# SparkFun_Music_Instrument_Shield.net
KiCad netlist of a schematic drawn in EAGLE
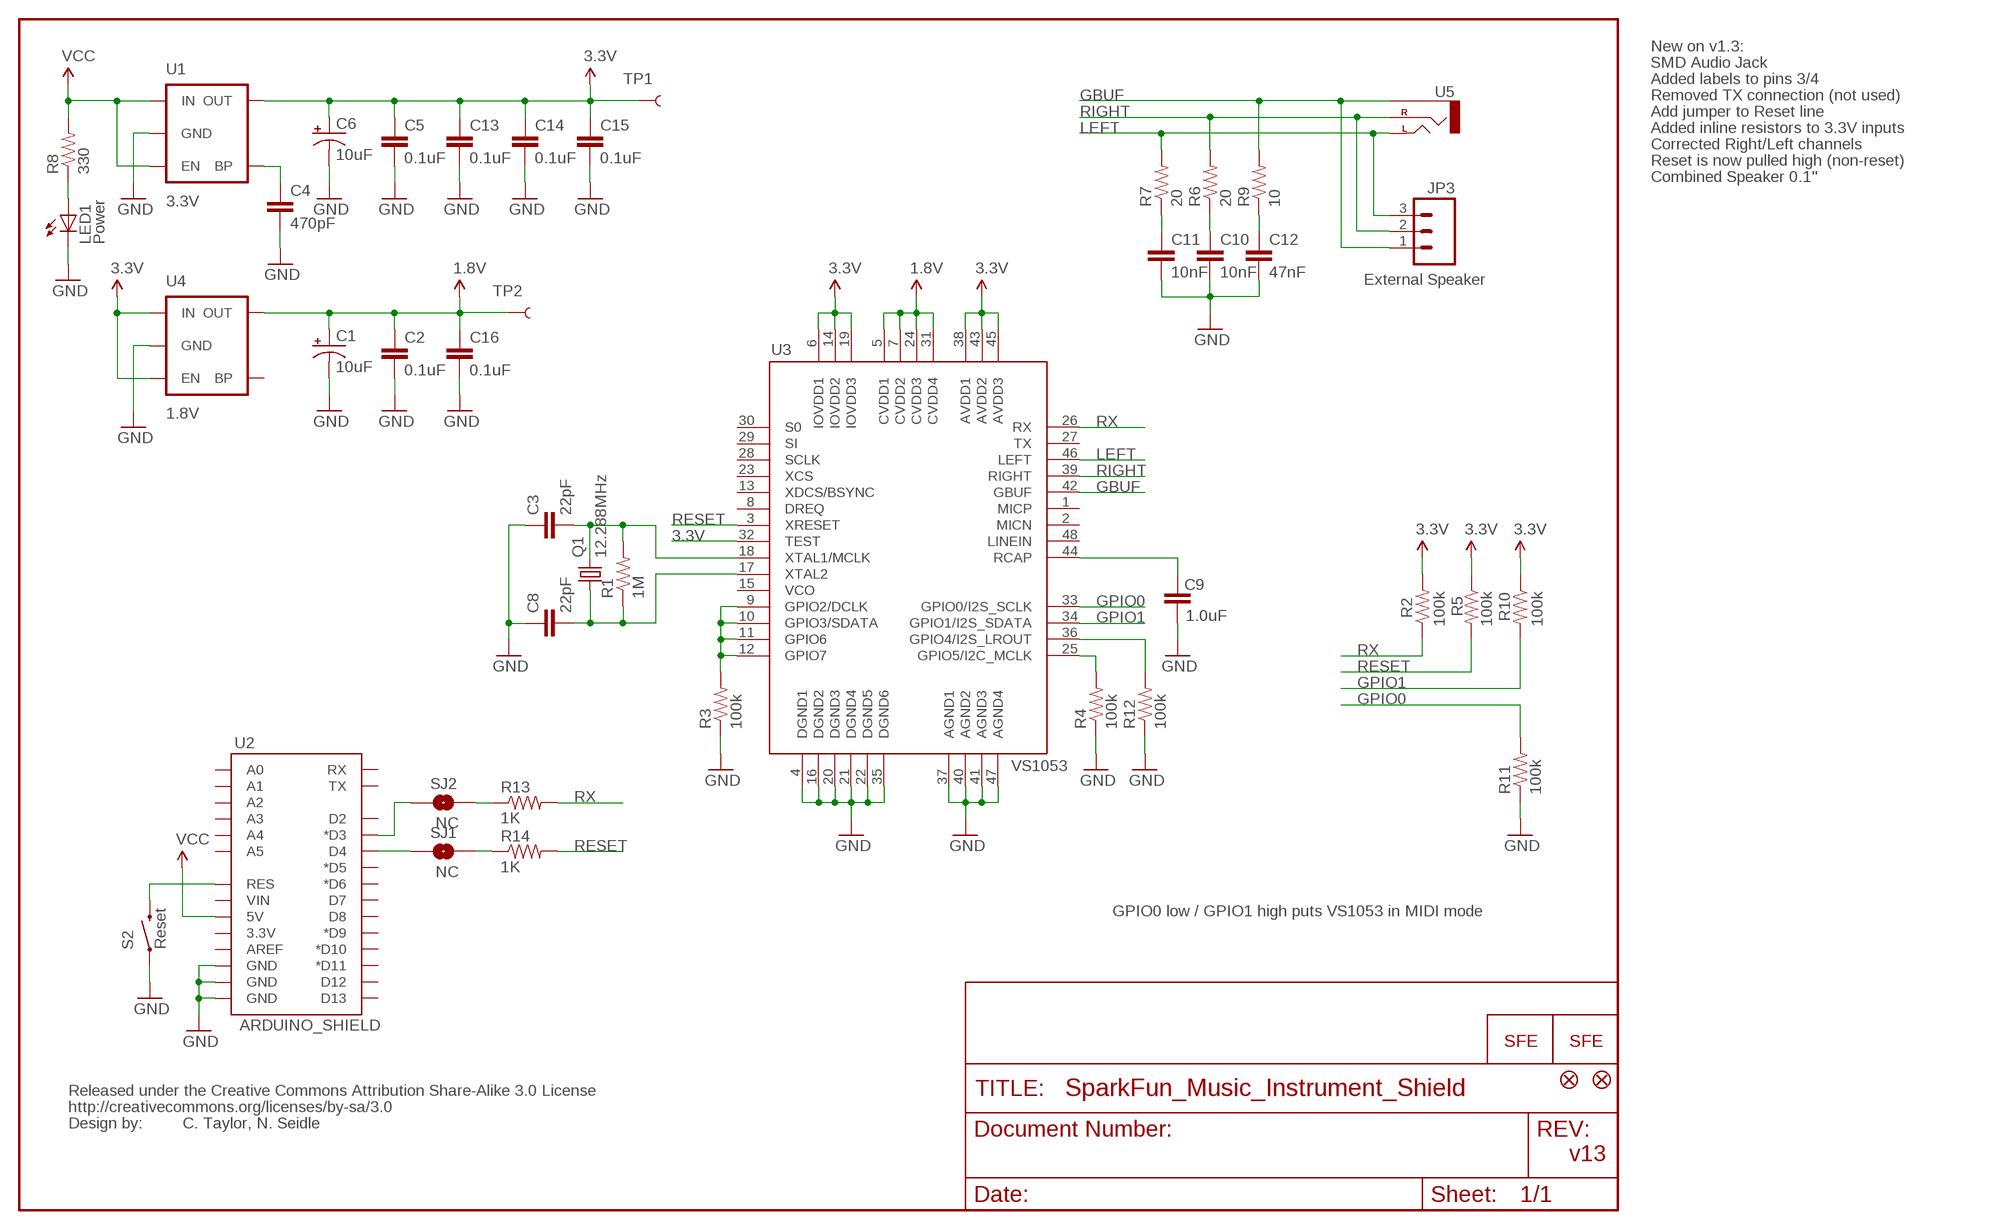
[diagram p0: schematic, sheet 1]

(export (version "E")
  (design (tool "Eeschema 10.0.6"))
  (components
    (comp (ref "C1")
      (value "10uF")
      (footprint "eagle-import:EIA3216")
      (libsource (lib "eagle-import") (part "CAP_POL1206"))
    )
    (comp (ref "C2")
      (value "0.1uF")
      (footprint "eagle-import:0402-CAP")
      (libsource (lib "eagle-import") (part "CAP0402-CAP"))
    )
    (comp (ref "C3")
      (value "22pF")
      (footprint "eagle-import:0402-CAP")
      (libsource (lib "eagle-import") (part "CAP0402-CAP"))
    )
    (comp (ref "C4")
      (value "470pF")
      (footprint "eagle-import:0402-CAP")
      (libsource (lib "eagle-import") (part "CAP0402-CAP"))
    )
    (comp (ref "C5")
      (value "0.1uF")
      (footprint "eagle-import:0402-CAP")
      (libsource (lib "eagle-import") (part "CAP0402-CAP"))
    )
    (comp (ref "C6")
      (value "10uF")
      (footprint "eagle-import:EIA3216")
      (libsource (lib "eagle-import") (part "CAP_POL1206"))
    )
    (comp (ref "C8")
      (value "22pF")
      (footprint "eagle-import:0402-CAP")
      (libsource (lib "eagle-import") (part "CAP0402-CAP"))
    )
    (comp (ref "C9")
      (value "1.0uF")
      (footprint "eagle-import:0402-CAP")
      (libsource (lib "eagle-import") (part "CAP0402-CAP"))
    )
    (comp (ref "C10")
      (value "10nF")
      (footprint "eagle-import:0402-CAP")
      (libsource (lib "eagle-import") (part "CAP0402-CAP"))
    )
    (comp (ref "C11")
      (value "10nF")
      (footprint "eagle-import:0402-CAP")
      (libsource (lib "eagle-import") (part "CAP0402-CAP"))
    )
    (comp (ref "C12")
      (value "47nF")
      (footprint "eagle-import:0402-CAP")
      (libsource (lib "eagle-import") (part "CAP0402-CAP"))
    )
    (comp (ref "C13")
      (value "0.1uF")
      (footprint "eagle-import:0402-CAP")
      (libsource (lib "eagle-import") (part "CAP0402-CAP"))
    )
    (comp (ref "C14")
      (value "0.1uF")
      (footprint "eagle-import:0402-CAP")
      (libsource (lib "eagle-import") (part "CAP0402-CAP"))
    )
    (comp (ref "C15")
      (value "0.1uF")
      (footprint "eagle-import:0402-CAP")
      (libsource (lib "eagle-import") (part "CAP0402-CAP"))
    )
    (comp (ref "C16")
      (value "0.1uF")
      (footprint "eagle-import:0402-CAP")
      (libsource (lib "eagle-import") (part "CAP0402-CAP"))
    )
    (comp (ref "JP3")
      (value "External Speaker")
      (footprint "eagle-import:1X03")
      (libsource (lib "eagle-import") (part "M03PTH"))
    )
    (comp (ref "LED1")
      (value "Power")
      (footprint "eagle-import:LED-0603")
      (libsource (lib "eagle-import") (part "LED0603"))
    )
    (comp (ref "Q1")
      (value "12.288MHz")
      (footprint "eagle-import:CRYSTAL-SMD-5X3")
      (libsource (lib "eagle-import") (part "CRYSTAL5X3"))
    )
    (comp (ref "R1")
      (value "1M")
      (footprint "eagle-import:0402-RES")
      (libsource (lib "eagle-import") (part "RESISTOR0402-RES"))
    )
    (comp (ref "R2")
      (value "100k")
      (footprint "eagle-import:0402-RES")
      (libsource (lib "eagle-import") (part "RESISTOR0402-RES"))
    )
    (comp (ref "R3")
      (value "100k")
      (footprint "eagle-import:0402-RES")
      (libsource (lib "eagle-import") (part "RESISTOR0402-RES"))
    )
    (comp (ref "R4")
      (value "100k")
      (footprint "eagle-import:0402-RES")
      (libsource (lib "eagle-import") (part "RESISTOR0402-RES"))
    )
    (comp (ref "R5")
      (value "100k")
      (footprint "eagle-import:0402-RES")
      (libsource (lib "eagle-import") (part "RESISTOR0402-RES"))
    )
    (comp (ref "R6")
      (value "20")
      (footprint "eagle-import:0402-RES")
      (libsource (lib "eagle-import") (part "RESISTOR0402-RES"))
    )
    (comp (ref "R7")
      (value "20")
      (footprint "eagle-import:0402-RES")
      (libsource (lib "eagle-import") (part "RESISTOR0402-RES"))
    )
    (comp (ref "R8")
      (value "330")
      (footprint "eagle-import:0402-RES")
      (libsource (lib "eagle-import") (part "RESISTOR0402-RES"))
    )
    (comp (ref "R9")
      (value "10")
      (footprint "eagle-import:0402-RES")
      (libsource (lib "eagle-import") (part "RESISTOR0402-RES"))
    )
    (comp (ref "R10")
      (value "100k")
      (footprint "eagle-import:0402-RES")
      (libsource (lib "eagle-import") (part "RESISTOR0402-RES"))
    )
    (comp (ref "R11")
      (value "100k")
      (footprint "eagle-import:0402-RES")
      (libsource (lib "eagle-import") (part "RESISTOR0402-RES"))
    )
    (comp (ref "R12")
      (value "100k")
      (footprint "eagle-import:0402-RES")
      (libsource (lib "eagle-import") (part "RESISTOR0402-RES"))
    )
    (comp (ref "R13")
      (value "1K")
      (footprint "eagle-import:0402-RES")
      (libsource (lib "eagle-import") (part "RESISTOR0402-RES"))
    )
    (comp (ref "R14")
      (value "1K")
      (footprint "eagle-import:0402-RES")
      (libsource (lib "eagle-import") (part "RESISTOR0402-RES"))
    )
    (comp (ref "S2")
      (value "Reset")
      (footprint "eagle-import:TACTILE_SWITCH_SMD")
      (libsource (lib "eagle-import") (part "SWITCH-MOMENTARY-2SMD"))
    )
    (comp (ref "SJ1")
      (value "NC")
      (footprint "eagle-import:SJ_2S-TRACE")
      (libsource (lib "eagle-import") (part "SOLDERJUMPERTRACE"))
    )
    (comp (ref "SJ2")
      (value "NC")
      (footprint "eagle-import:SJ_2S-TRACE")
      (libsource (lib "eagle-import") (part "SOLDERJUMPERTRACE"))
    )
    (comp (ref "TP1")
      (value "TEST-POINT3X5")
      (footprint "eagle-import:PAD.03X.05")
      (libsource (lib "eagle-import") (part "TEST-POINT3X5"))
    )
    (comp (ref "TP2")
      (value "TEST-POINT3X5")
      (footprint "eagle-import:PAD.03X.05")
      (libsource (lib "eagle-import") (part "TEST-POINT3X5"))
    )
    (comp (ref "U$3")
      (value "CREATIVE_COMMONS")
      (footprint "eagle-import:CREATIVE_COMMONS")
      (libsource (lib "eagle-import") (part "CREATIVE_COMMONS"))
    )
    (comp (ref "U$4")
      (value "FIDUCIAL1X2")
      (footprint "eagle-import:FIDUCIAL-1X2")
      (libsource (lib "eagle-import") (part "FIDUCIAL1X2"))
    )
    (comp (ref "U$5")
      (value "FIDUCIAL1X2")
      (footprint "eagle-import:FIDUCIAL-1X2")
      (libsource (lib "eagle-import") (part "FIDUCIAL1X2"))
    )
    (comp (ref "U$7")
      (value "LOGO-SFENEW")
      (footprint "eagle-import:SFE-NEW-WEBLOGO")
      (libsource (lib "eagle-import") (part "LOGO-SFENEW"))
    )
    (comp (ref "U$8")
      (value "LOGO-SFENEW")
      (footprint "eagle-import:SFE-NEW-WEBLOGO")
      (libsource (lib "eagle-import") (part "LOGO-SFENEW"))
    )
    (comp (ref "U1")
      (value "3.3V")
      (footprint "eagle-import:SOT23-5")
      (libsource (lib "eagle-import") (part "V_REG_LDOSMD"))
    )
    (comp (ref "U2")
      (value "ARDUINO_SHIELD")
      (footprint "eagle-import:DUEMILANOVE_SHIELD")
      (libsource (lib "eagle-import") (part "ARDUINO_SHIELDLABEL"))
    )
    (comp (ref "U3")
      (value "VS1053")
      (footprint "eagle-import:LQFP-48")
      (libsource (lib "eagle-import") (part "VS1033"))
    )
    (comp (ref "U4")
      (value "1.8V")
      (footprint "eagle-import:SC70")
      (libsource (lib "eagle-import") (part "V_REG_LDOSMD2"))
    )
    (comp (ref "U5")
      (value "AUDIO-JACKSMD2")
      (footprint "eagle-import:AUDIO-JACK-3.5MM-SMD")
      (libsource (lib "eagle-import") (part "AUDIO-JACKSMD2"))
    )
  )
  (nets
    (net (code "1") (name "/GBUF") (class "Default")
      (node (ref "JP3") (pin "1") (pinfunction "1_1") (pintype "passive"))
      (node (ref "R9") (pin "2") (pinfunction "2_2") (pintype "passive"))
      (node (ref "U3") (pin "42") (pinfunction "GBUF_42") (pintype "bidirectional"))
      (node (ref "U5") (pin "SLEEVE") (pinfunction "SLEEVE_SLEEVE") (pintype "bidirectional"))
    )
    (net (code "2") (name "/GPIO0") (class "Default")
      (node (ref "R11") (pin "2") (pinfunction "2_2") (pintype "passive"))
      (node (ref "U3") (pin "33") (pinfunction "GPIO0/I2S_SCLK_33") (pintype "bidirectional"))
    )
    (net (code "3") (name "/GPIO1") (class "Default")
      (node (ref "R10") (pin "2") (pinfunction "2_2") (pintype "passive"))
      (node (ref "U3") (pin "34") (pinfunction "GPIO1/I2S_SDATA_34") (pintype "bidirectional"))
    )
    (net (code "4") (name "/LEFT") (class "Default")
      (node (ref "JP3") (pin "3") (pinfunction "3_3") (pintype "passive"))
      (node (ref "R7") (pin "2") (pinfunction "2_2") (pintype "passive"))
      (node (ref "U3") (pin "46") (pinfunction "LEFT_46") (pintype "bidirectional"))
      (node (ref "U5") (pin "TIP") (pinfunction "LEFT_TIP") (pintype "bidirectional"))
    )
    (net (code "5") (name "/RESET") (class "Default")
      (node (ref "R14") (pin "2") (pinfunction "2_2") (pintype "passive"))
      (node (ref "R5") (pin "2") (pinfunction "2_2") (pintype "passive"))
      (node (ref "U3") (pin "3") (pinfunction "XRESET_3") (pintype "bidirectional"))
    )
    (net (code "6") (name "/RIGHT") (class "Default")
      (node (ref "JP3") (pin "2") (pinfunction "2_2") (pintype "passive"))
      (node (ref "R6") (pin "2") (pinfunction "2_2") (pintype "passive"))
      (node (ref "U3") (pin "39") (pinfunction "RIGHT_39") (pintype "bidirectional"))
      (node (ref "U5") (pin "RING") (pinfunction "RIGHT_RING") (pintype "bidirectional"))
    )
    (net (code "7") (name "/RX") (class "Default")
      (node (ref "R13") (pin "2") (pinfunction "2_2") (pintype "passive"))
      (node (ref "R2") (pin "1") (pinfunction "1_1") (pintype "passive"))
      (node (ref "U3") (pin "26") (pinfunction "RX_26") (pintype "bidirectional"))
    )
    (net (code "8") (name "1.8V") (class "Default")
      (node (ref "C1") (pin "A") (pinfunction "+_A") (pintype "passive"))
      (node (ref "C16") (pin "1") (pinfunction "1_1") (pintype "passive"))
      (node (ref "C2") (pin "1") (pinfunction "1_1") (pintype "passive"))
      (node (ref "TP2") (pin "P$1") (pinfunction "1_P$1") (pintype "bidirectional"))
      (node (ref "U3") (pin "24") (pinfunction "CVDD3_24") (pintype "bidirectional"))
      (node (ref "U3") (pin "31") (pinfunction "CVDD4_31") (pintype "bidirectional"))
      (node (ref "U3") (pin "5") (pinfunction "CVDD1_5") (pintype "bidirectional"))
      (node (ref "U3") (pin "7") (pinfunction "CVDD2_7") (pintype "bidirectional"))
      (node (ref "U4") (pin "5") (pinfunction "OUT_5") (pintype "passive"))
    )
    (net (code "9") (name "3.3V") (class "Default")
      (node (ref "C13") (pin "1") (pinfunction "1_1") (pintype "passive"))
      (node (ref "C14") (pin "1") (pinfunction "1_1") (pintype "passive"))
      (node (ref "C15") (pin "1") (pinfunction "1_1") (pintype "passive"))
      (node (ref "C5") (pin "1") (pinfunction "1_1") (pintype "passive"))
      (node (ref "C6") (pin "A") (pinfunction "+_A") (pintype "passive"))
      (node (ref "R10") (pin "1") (pinfunction "1_1") (pintype "passive"))
      (node (ref "R2") (pin "2") (pinfunction "2_2") (pintype "passive"))
      (node (ref "R5") (pin "1") (pinfunction "1_1") (pintype "passive"))
      (node (ref "TP1") (pin "P$1") (pinfunction "1_P$1") (pintype "bidirectional"))
      (node (ref "U1") (pin "5") (pinfunction "OUT_5") (pintype "passive"))
      (node (ref "U3") (pin "14") (pinfunction "IOVDD2_14") (pintype "bidirectional"))
      (node (ref "U3") (pin "19") (pinfunction "IOVDD3_19") (pintype "bidirectional"))
      (node (ref "U3") (pin "32") (pinfunction "TEST_32") (pintype "bidirectional"))
      (node (ref "U3") (pin "38") (pinfunction "AVDD1_38") (pintype "bidirectional"))
      (node (ref "U3") (pin "43") (pinfunction "AVDD2_43") (pintype "bidirectional"))
      (node (ref "U3") (pin "45") (pinfunction "AVDD3_45") (pintype "bidirectional"))
      (node (ref "U3") (pin "6") (pinfunction "IOVDD1_6") (pintype "bidirectional"))
      (node (ref "U4") (pin "1") (pinfunction "IN_1") (pintype "input"))
      (node (ref "U4") (pin "3") (pinfunction "EN_3") (pintype "input"))
    )
    (net (code "10") (name "GND") (class "Default")
      (node (ref "C1") (pin "C") (pinfunction "-_C") (pintype "passive"))
      (node (ref "C10") (pin "2") (pinfunction "2_2") (pintype "passive"))
      (node (ref "C11") (pin "2") (pinfunction "2_2") (pintype "passive"))
      (node (ref "C12") (pin "2") (pinfunction "2_2") (pintype "passive"))
      (node (ref "C13") (pin "2") (pinfunction "2_2") (pintype "passive"))
      (node (ref "C14") (pin "2") (pinfunction "2_2") (pintype "passive"))
      (node (ref "C15") (pin "2") (pinfunction "2_2") (pintype "passive"))
      (node (ref "C16") (pin "2") (pinfunction "2_2") (pintype "passive"))
      (node (ref "C2") (pin "2") (pinfunction "2_2") (pintype "passive"))
      (node (ref "C3") (pin "1") (pinfunction "1_1") (pintype "passive"))
      (node (ref "C4") (pin "2") (pinfunction "2_2") (pintype "passive"))
      (node (ref "C5") (pin "2") (pinfunction "2_2") (pintype "passive"))
      (node (ref "C6") (pin "C") (pinfunction "-_C") (pintype "passive"))
      (node (ref "C8") (pin "1") (pinfunction "1_1") (pintype "passive"))
      (node (ref "C9") (pin "1") (pinfunction "1_1") (pintype "passive"))
      (node (ref "LED1") (pin "C") (pinfunction "C_C") (pintype "passive"))
      (node (ref "R11") (pin "1") (pinfunction "1_1") (pintype "passive"))
      (node (ref "R12") (pin "1") (pinfunction "1_1") (pintype "passive"))
      (node (ref "R3") (pin "1") (pinfunction "1_1") (pintype "passive"))
      (node (ref "R4") (pin "1") (pinfunction "1_1") (pintype "passive"))
      (node (ref "S2") (pin "1") (pinfunction "1_1") (pintype "passive"))
      (node (ref "U1") (pin "2") (pinfunction "GND_2") (pintype "input"))
      (node (ref "U2") (pin "GND@0") (pinfunction "GND_GND@0") (pintype "bidirectional"))
      (node (ref "U2") (pin "GND@1") (pinfunction "GND_GND@1") (pintype "bidirectional"))
      (node (ref "U2") (pin "GND@2") (pinfunction "GND_GND@2") (pintype "bidirectional"))
      (node (ref "U3") (pin "16") (pinfunction "DGND2_16") (pintype "bidirectional"))
      (node (ref "U3") (pin "20") (pinfunction "DGND3_20") (pintype "bidirectional"))
      (node (ref "U3") (pin "21") (pinfunction "DGND4_21") (pintype "bidirectional"))
      (node (ref "U3") (pin "22") (pinfunction "DGND5_22") (pintype "bidirectional"))
      (node (ref "U3") (pin "35") (pinfunction "DGND6_35") (pintype "bidirectional"))
      (node (ref "U3") (pin "37") (pinfunction "AGND1_37") (pintype "bidirectional"))
      (node (ref "U3") (pin "4") (pinfunction "DGND1_4") (pintype "bidirectional"))
      (node (ref "U3") (pin "40") (pinfunction "AGND2_40") (pintype "bidirectional"))
      (node (ref "U3") (pin "41") (pinfunction "AGND3_41") (pintype "bidirectional"))
      (node (ref "U3") (pin "47") (pinfunction "AGND4_47") (pintype "bidirectional"))
      (node (ref "U4") (pin "2") (pinfunction "GND_2") (pintype "input"))
    )
    (net (code "11") (name "Net-(C10-Pad1)") (class "Default")
      (node (ref "C10") (pin "1") (pinfunction "1_1") (pintype "passive"))
      (node (ref "R6") (pin "1") (pinfunction "1_1") (pintype "passive"))
    )
    (net (code "12") (name "Net-(C11-Pad1)") (class "Default")
      (node (ref "C11") (pin "1") (pinfunction "1_1") (pintype "passive"))
      (node (ref "R7") (pin "1") (pinfunction "1_1") (pintype "passive"))
    )
    (net (code "13") (name "Net-(C12-Pad1)") (class "Default")
      (node (ref "C12") (pin "1") (pinfunction "1_1") (pintype "passive"))
      (node (ref "R9") (pin "1") (pinfunction "1_1") (pintype "passive"))
    )
    (net (code "14") (name "Net-(LED1-PadA)") (class "Default")
      (node (ref "LED1") (pin "A") (pinfunction "A_A") (pintype "passive"))
      (node (ref "R8") (pin "1") (pinfunction "1_1") (pintype "passive"))
    )
    (net (code "15") (name "Net-(Q1-2)") (class "Default")
      (node (ref "C3") (pin "2") (pinfunction "2_2") (pintype "passive"))
      (node (ref "Q1") (pin "3") (pinfunction "2_3") (pintype "passive"))
      (node (ref "R1") (pin "2") (pinfunction "2_2") (pintype "passive"))
      (node (ref "U3") (pin "18") (pinfunction "XTAL1/MCLK_18") (pintype "bidirectional"))
    )
    (net (code "16") (name "Net-(R13-Pad1)") (class "Default")
      (node (ref "R13") (pin "1") (pinfunction "1_1") (pintype "passive"))
      (node (ref "SJ2") (pin "2") (pinfunction "2_2") (pintype "passive"))
    )
    (net (code "17") (name "Net-(R14-Pad1)") (class "Default")
      (node (ref "R14") (pin "1") (pinfunction "1_1") (pintype "passive"))
      (node (ref "SJ1") (pin "2") (pinfunction "2_2") (pintype "passive"))
    )
    (net (code "18") (name "Net-(S2-2)") (class "Default")
      (node (ref "S2") (pin "3") (pinfunction "2_3") (pintype "passive"))
      (node (ref "U2") (pin "RES") (pinfunction "RES_RES") (pintype "bidirectional"))
    )
    (net (code "19") (name "Net-(SJ1-Pad1)") (class "Default")
      (node (ref "SJ1") (pin "1") (pinfunction "1_1") (pintype "passive"))
      (node (ref "U2") (pin "D4") (pinfunction "D4_D4") (pintype "bidirectional"))
    )
    (net (code "20") (name "Net-(U1-BP)") (class "Default")
      (node (ref "C4") (pin "1") (pinfunction "1_1") (pintype "passive"))
      (node (ref "U1") (pin "4") (pinfunction "BP_4") (pintype "input"))
    )
    (net (code "21") (name "Net-(U2-*D3)") (class "Default")
      (node (ref "SJ2") (pin "1") (pinfunction "1_1") (pintype "passive"))
      (node (ref "U2") (pin "D3") (pinfunction "*D3_D3") (pintype "bidirectional"))
    )
    (net (code "22") (name "Net-(U3-GPIO2{slash}DCLK)") (class "Default")
      (node (ref "R3") (pin "2") (pinfunction "2_2") (pintype "passive"))
      (node (ref "U3") (pin "10") (pinfunction "GPIO3/SDATA_10") (pintype "bidirectional"))
      (node (ref "U3") (pin "11") (pinfunction "GPIO6_11") (pintype "bidirectional"))
      (node (ref "U3") (pin "12") (pinfunction "GPIO7_12") (pintype "bidirectional"))
      (node (ref "U3") (pin "9") (pinfunction "GPIO2/DCLK_9") (pintype "bidirectional"))
    )
    (net (code "23") (name "Net-(U3-GPIO4{slash}I2S_LROUT)") (class "Default")
      (node (ref "R12") (pin "2") (pinfunction "2_2") (pintype "passive"))
      (node (ref "U3") (pin "36") (pinfunction "GPIO4/I2S_LROUT_36") (pintype "bidirectional"))
    )
    (net (code "24") (name "Net-(U3-GPIO5{slash}I2C_MCLK)") (class "Default")
      (node (ref "R4") (pin "2") (pinfunction "2_2") (pintype "passive"))
      (node (ref "U3") (pin "25") (pinfunction "GPIO5/I2C_MCLK_25") (pintype "bidirectional"))
    )
    (net (code "25") (name "Net-(U3-RCAP)") (class "Default")
      (node (ref "C9") (pin "2") (pinfunction "2_2") (pintype "passive"))
      (node (ref "U3") (pin "44") (pinfunction "RCAP_44") (pintype "bidirectional"))
    )
    (net (code "26") (name "Net-(U3-XTAL2)") (class "Default")
      (node (ref "C8") (pin "2") (pinfunction "2_2") (pintype "passive"))
      (node (ref "Q1") (pin "1") (pinfunction "1_1") (pintype "passive"))
      (node (ref "R1") (pin "1") (pinfunction "1_1") (pintype "passive"))
      (node (ref "U3") (pin "17") (pinfunction "XTAL2_17") (pintype "bidirectional"))
    )
    (net (code "27") (name "VCC") (class "Default")
      (node (ref "R8") (pin "2") (pinfunction "2_2") (pintype "passive"))
      (node (ref "U1") (pin "1") (pinfunction "IN_1") (pintype "input"))
      (node (ref "U1") (pin "3") (pinfunction "EN_3") (pintype "input"))
      (node (ref "U2") (pin "5V") (pinfunction "5V_5V") (pintype "bidirectional"))
    )
    (net (code "28") (name "unconnected-(U2-*D5-PadD5)") (class "Default")
      (node (ref "U2") (pin "D5") (pinfunction "*D5_D5") (pintype "bidirectional"))
    )
    (net (code "29") (name "unconnected-(U2-*D6-PadD6)") (class "Default")
      (node (ref "U2") (pin "D6") (pinfunction "*D6_D6") (pintype "bidirectional"))
    )
    (net (code "30") (name "unconnected-(U2-*D9-PadD9)") (class "Default")
      (node (ref "U2") (pin "D9") (pinfunction "*D9_D9") (pintype "bidirectional"))
    )
    (net (code "31") (name "unconnected-(U2-*D10-PadD10)") (class "Default")
      (node (ref "U2") (pin "D10") (pinfunction "*D10_D10") (pintype "bidirectional"))
    )
    (net (code "32") (name "unconnected-(U2-*D11-PadD11)") (class "Default")
      (node (ref "U2") (pin "D11") (pinfunction "*D11_D11") (pintype "bidirectional"))
    )
    (net (code "33") (name "unconnected-(U2-Pad3.3V)") (class "Default")
      (node (ref "U2") (pin "3.3V") (pinfunction "3.3V_3.3V") (pintype "bidirectional"))
    )
    (net (code "34") (name "unconnected-(U2-PadA0)") (class "Default")
      (node (ref "U2") (pin "A0") (pinfunction "A0_A0") (pintype "bidirectional"))
    )
    (net (code "35") (name "unconnected-(U2-PadA1)") (class "Default")
      (node (ref "U2") (pin "A1") (pinfunction "A1_A1") (pintype "bidirectional"))
    )
    (net (code "36") (name "unconnected-(U2-PadA2)") (class "Default")
      (node (ref "U2") (pin "A2") (pinfunction "A2_A2") (pintype "bidirectional"))
    )
    (net (code "37") (name "unconnected-(U2-PadA3)") (class "Default")
      (node (ref "U2") (pin "A3") (pinfunction "A3_A3") (pintype "bidirectional"))
    )
    (net (code "38") (name "unconnected-(U2-PadA4)") (class "Default")
      (node (ref "U2") (pin "A4") (pinfunction "A4_A4") (pintype "bidirectional"))
    )
    (net (code "39") (name "unconnected-(U2-PadA5)") (class "Default")
      (node (ref "U2") (pin "A5") (pinfunction "A5_A5") (pintype "bidirectional"))
    )
    (net (code "40") (name "unconnected-(U2-PadAREF)") (class "Default")
      (node (ref "U2") (pin "AREF") (pinfunction "AREF_AREF") (pintype "bidirectional"))
    )
    (net (code "41") (name "unconnected-(U2-PadD2)") (class "Default")
      (node (ref "U2") (pin "D2") (pinfunction "D2_D2") (pintype "bidirectional"))
    )
    (net (code "42") (name "unconnected-(U2-PadD7)") (class "Default")
      (node (ref "U2") (pin "D7") (pinfunction "D7_D7") (pintype "bidirectional"))
    )
    (net (code "43") (name "unconnected-(U2-PadD8)") (class "Default")
      (node (ref "U2") (pin "D8") (pinfunction "D8_D8") (pintype "bidirectional"))
    )
    (net (code "44") (name "unconnected-(U2-PadD12)") (class "Default")
      (node (ref "U2") (pin "D12") (pinfunction "D12_D12") (pintype "bidirectional"))
    )
    (net (code "45") (name "unconnected-(U2-PadD13)") (class "Default")
      (node (ref "U2") (pin "D13") (pinfunction "D13_D13") (pintype "bidirectional"))
    )
    (net (code "46") (name "unconnected-(U2-PadRX)") (class "Default")
      (node (ref "U2") (pin "RX") (pinfunction "RX_RX") (pintype "bidirectional"))
    )
    (net (code "47") (name "unconnected-(U2-PadTX)") (class "Default")
      (node (ref "U2") (pin "TX") (pinfunction "TX_TX") (pintype "bidirectional"))
    )
    (net (code "48") (name "unconnected-(U2-PadVIN)") (class "Default")
      (node (ref "U2") (pin "VIN") (pinfunction "VIN_VIN") (pintype "bidirectional"))
    )
    (net (code "49") (name "unconnected-(U3-DREQ-Pad8)") (class "Default")
      (node (ref "U3") (pin "8") (pinfunction "DREQ_8") (pintype "bidirectional"))
    )
    (net (code "50") (name "unconnected-(U3-LINEIN-Pad48)") (class "Default")
      (node (ref "U3") (pin "48") (pinfunction "LINEIN_48") (pintype "bidirectional"))
    )
    (net (code "51") (name "unconnected-(U3-MICN-Pad2)") (class "Default")
      (node (ref "U3") (pin "2") (pinfunction "MICN_2") (pintype "bidirectional"))
    )
    (net (code "52") (name "unconnected-(U3-MICP-Pad1)") (class "Default")
      (node (ref "U3") (pin "1") (pinfunction "MICP_1") (pintype "bidirectional"))
    )
    (net (code "53") (name "unconnected-(U3-S0-Pad30)") (class "Default")
      (node (ref "U3") (pin "30") (pinfunction "S0_30") (pintype "bidirectional"))
    )
    (net (code "54") (name "unconnected-(U3-SCLK-Pad28)") (class "Default")
      (node (ref "U3") (pin "28") (pinfunction "SCLK_28") (pintype "bidirectional"))
    )
    (net (code "55") (name "unconnected-(U3-SI-Pad29)") (class "Default")
      (node (ref "U3") (pin "29") (pinfunction "SI_29") (pintype "bidirectional"))
    )
    (net (code "56") (name "unconnected-(U3-TX-Pad27)") (class "Default")
      (node (ref "U3") (pin "27") (pinfunction "TX_27") (pintype "bidirectional"))
    )
    (net (code "57") (name "unconnected-(U3-VCO-Pad15)") (class "Default")
      (node (ref "U3") (pin "15") (pinfunction "VCO_15") (pintype "bidirectional"))
    )
    (net (code "58") (name "unconnected-(U3-XCS-Pad23)") (class "Default")
      (node (ref "U3") (pin "23") (pinfunction "XCS_23") (pintype "bidirectional"))
    )
    (net (code "59") (name "unconnected-(U3-XDCS{slash}BSYNC-Pad13)") (class "Default")
      (node (ref "U3") (pin "13") (pinfunction "XDCS/BSYNC_13") (pintype "bidirectional"))
    )
    (net (code "60") (name "unconnected-(U4-BP-Pad4)") (class "Default")
      (node (ref "U4") (pin "4") (pinfunction "BP_4") (pintype "input"))
    )
  )
)
